# hive_module.net
KiCad netlist of a schematic drawn in EAGLE
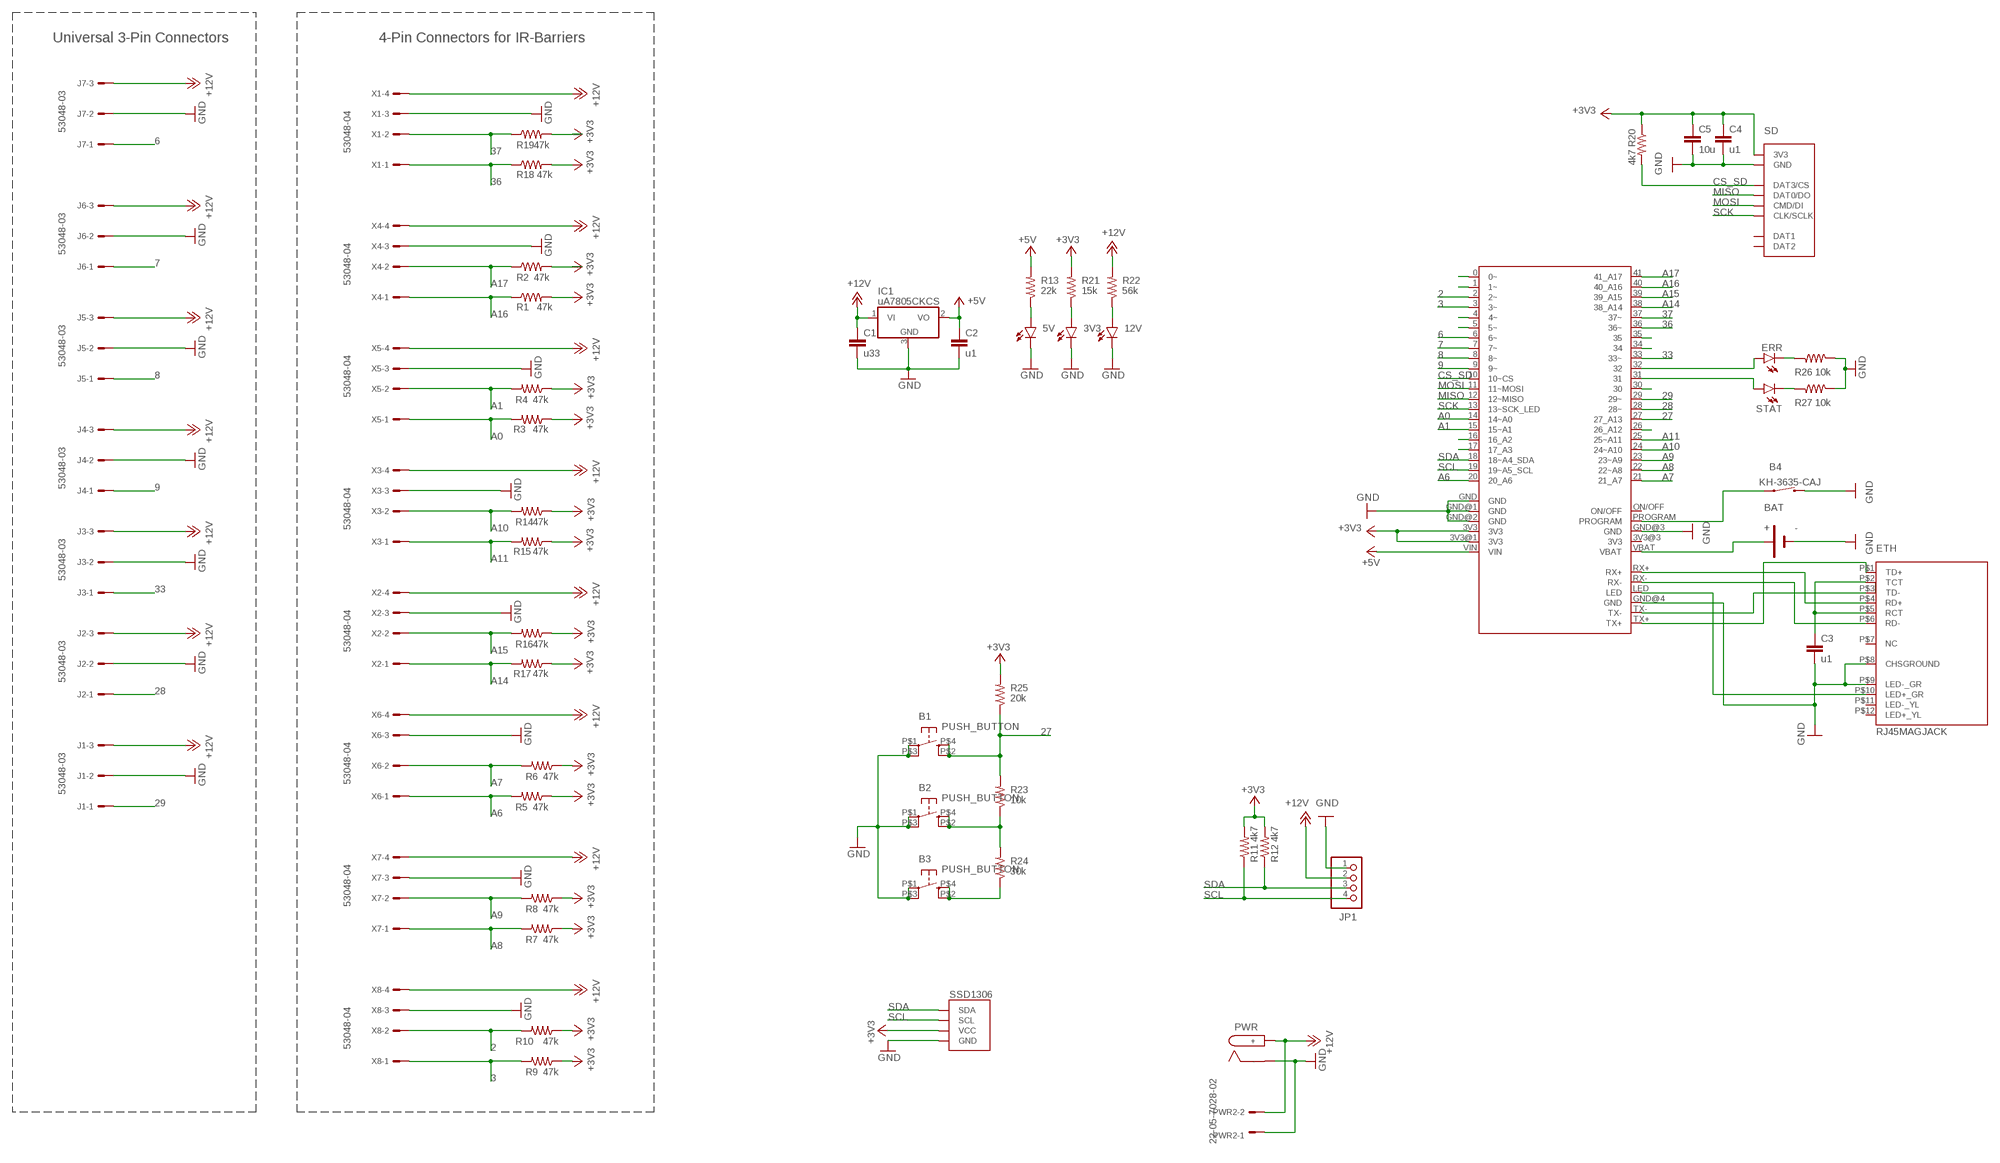
[diagram p0: schematic, sheet 1]

(export (version "E")
  (design (tool "Eeschema 10.0.6"))
  (components
    (comp (ref "3V3")
      (value "LEDCHIP-LED0805")
      (footprint "eagle-import:CHIP-LED0805")
      (libsource (lib "eagle-import") (part "LEDCHIP-LED0805"))
    )
    (comp (ref "5V")
      (value "LEDCHIP-LED0805")
      (footprint "eagle-import:CHIP-LED0805")
      (libsource (lib "eagle-import") (part "LEDCHIP-LED0805"))
    )
    (comp (ref "12V")
      (value "LEDCHIP-LED0805")
      (footprint "eagle-import:CHIP-LED0805")
      (libsource (lib "eagle-import") (part "LEDCHIP-LED0805"))
    )
    (comp (ref "B1")
      (value "PUSH_BUTTON")
      (footprint "eagle-import:PUSH_BUTTON")
      (libsource (lib "eagle-import") (part "PUSH_BUTTON"))
    )
    (comp (ref "B2")
      (value "PUSH_BUTTON")
      (footprint "eagle-import:PUSH_BUTTON")
      (libsource (lib "eagle-import") (part "PUSH_BUTTON"))
    )
    (comp (ref "B3")
      (value "PUSH_BUTTON")
      (footprint "eagle-import:PUSH_BUTTON")
      (libsource (lib "eagle-import") (part "PUSH_BUTTON"))
    )
    (comp (ref "B4")
      (value "KH-3635-CAJ")
      (footprint "eagle-import:KH-3635-CAJ")
      (libsource (lib "eagle-import") (part "KH-3635-CAJ"))
    )
    (comp (ref "BAT")
      (value "BS-08-B2AA002")
      (footprint "eagle-import:BS-08-B2AA002")
      (libsource (lib "eagle-import") (part "BS-08-B2AA002"))
    )
    (comp (ref "C1")
      (value "u33")
      (footprint "eagle-import:C0805")
      (libsource (lib "eagle-import") (part "C-EUC0805"))
    )
    (comp (ref "C2")
      (value "u1")
      (footprint "eagle-import:C0805")
      (libsource (lib "eagle-import") (part "C-EUC0805"))
    )
    (comp (ref "C3")
      (value "u1")
      (footprint "eagle-import:C0805")
      (libsource (lib "eagle-import") (part "C-EUC0805"))
    )
    (comp (ref "C4")
      (value "u1")
      (footprint "eagle-import:C0805")
      (libsource (lib "eagle-import") (part "C-EUC0805"))
    )
    (comp (ref "C5")
      (value "10u")
      (footprint "eagle-import:C0805")
      (libsource (lib "eagle-import") (part "C-EUC0805"))
    )
    (comp (ref "ERR")
      (value "LEDCHIP-LED0805")
      (footprint "eagle-import:CHIP-LED0805")
      (libsource (lib "eagle-import") (part "LEDCHIP-LED0805"))
    )
    (comp (ref "ETH")
      (value "RJ45MAGJACK")
      (footprint "eagle-import:LPJ4012AHNL")
      (libsource (lib "eagle-import") (part "RJ45MAGJACK"))
    )
    (comp (ref "IC1")
      (value "uA7805CKCS")
      (footprint "eagle-import:TO252")
      (libsource (lib "eagle-import") (part "7805_TO252"))
    )
    (comp (ref "J1")
      (value "53048-03")
      (footprint "eagle-import:53048-03")
      (fields (field (name "MF") "WALDOM/MOLEX") (field (name "MPN") "53048-0310"))
      (libsource (lib "eagle-import") (part "53?-03048"))
    )
    (comp (ref "J2")
      (value "53048-03")
      (footprint "eagle-import:53048-03")
      (fields (field (name "MF") "WALDOM/MOLEX") (field (name "MPN") "53048-0310"))
      (libsource (lib "eagle-import") (part "53?-03048"))
    )
    (comp (ref "J3")
      (value "53048-03")
      (footprint "eagle-import:53048-03")
      (fields (field (name "MF") "WALDOM/MOLEX") (field (name "MPN") "53048-0310"))
      (libsource (lib "eagle-import") (part "53?-03048"))
    )
    (comp (ref "J4")
      (value "53048-03")
      (footprint "eagle-import:53048-03")
      (fields (field (name "MF") "WALDOM/MOLEX") (field (name "MPN") "53048-0310"))
      (libsource (lib "eagle-import") (part "53?-03048"))
    )
    (comp (ref "J5")
      (value "53048-03")
      (footprint "eagle-import:53048-03")
      (fields (field (name "MF") "WALDOM/MOLEX") (field (name "MPN") "53048-0310"))
      (libsource (lib "eagle-import") (part "53?-03048"))
    )
    (comp (ref "J6")
      (value "53048-03")
      (footprint "eagle-import:53048-03")
      (fields (field (name "MF") "WALDOM/MOLEX") (field (name "MPN") "53048-0310"))
      (libsource (lib "eagle-import") (part "53?-03048"))
    )
    (comp (ref "J7")
      (value "53048-03")
      (footprint "eagle-import:53048-03")
      (fields (field (name "MF") "WALDOM/MOLEX") (field (name "MPN") "53048-0310"))
      (libsource (lib "eagle-import") (part "53?-03048"))
    )
    (comp (ref "JP1")
      (value "PINHD-1X4")
      (footprint "eagle-import:1X04")
      (libsource (lib "eagle-import") (part "PINHD-1X4"))
    )
    (comp (ref "PWR")
      (value "DC-042C-Z-2.5-A")
      (footprint "eagle-import:DC-042C-Z-2.5-A")
      (libsource (lib "eagle-import") (part "DC-042C-Z-2.5-A"))
    )
    (comp (ref "PWR2")
      (value "22-05-7028-02")
      (footprint "eagle-import:7395-02")
      (fields (field (name "MF") "MOLEX"))
      (libsource (lib "eagle-import") (part "22-?-0205-7028"))
    )
    (comp (ref "R1")
      (value "47k")
      (footprint "eagle-import:R0805")
      (libsource (lib "eagle-import") (part "R-US_R0805"))
    )
    (comp (ref "R2")
      (value "47k")
      (footprint "eagle-import:R0805")
      (libsource (lib "eagle-import") (part "R-US_R0805"))
    )
    (comp (ref "R3")
      (value "47k")
      (footprint "eagle-import:R0805")
      (libsource (lib "eagle-import") (part "R-US_R0805"))
    )
    (comp (ref "R4")
      (value "47k")
      (footprint "eagle-import:R0805")
      (libsource (lib "eagle-import") (part "R-US_R0805"))
    )
    (comp (ref "R5")
      (value "47k")
      (footprint "eagle-import:R0805")
      (libsource (lib "eagle-import") (part "R-US_R0805"))
    )
    (comp (ref "R6")
      (value "47k")
      (footprint "eagle-import:R0805")
      (libsource (lib "eagle-import") (part "R-US_R0805"))
    )
    (comp (ref "R7")
      (value "47k")
      (footprint "eagle-import:R0805")
      (libsource (lib "eagle-import") (part "R-US_R0805"))
    )
    (comp (ref "R8")
      (value "47k")
      (footprint "eagle-import:R0805")
      (libsource (lib "eagle-import") (part "R-US_R0805"))
    )
    (comp (ref "R9")
      (value "47k")
      (footprint "eagle-import:R0805")
      (libsource (lib "eagle-import") (part "R-US_R0805"))
    )
    (comp (ref "R10")
      (value "47k")
      (footprint "eagle-import:R0805")
      (libsource (lib "eagle-import") (part "R-US_R0805"))
    )
    (comp (ref "R11")
      (value "4k7")
      (footprint "eagle-import:R0805")
      (libsource (lib "eagle-import") (part "R-US_R0805"))
    )
    (comp (ref "R12")
      (value "4k7")
      (footprint "eagle-import:R0805")
      (libsource (lib "eagle-import") (part "R-US_R0805"))
    )
    (comp (ref "R13")
      (value "22k")
      (footprint "eagle-import:R0805")
      (libsource (lib "eagle-import") (part "R-US_R0805"))
    )
    (comp (ref "R14")
      (value "47k")
      (footprint "eagle-import:R0805")
      (libsource (lib "eagle-import") (part "R-US_R0805"))
    )
    (comp (ref "R15")
      (value "47k")
      (footprint "eagle-import:R0805")
      (libsource (lib "eagle-import") (part "R-US_R0805"))
    )
    (comp (ref "R16")
      (value "47k")
      (footprint "eagle-import:R0805")
      (libsource (lib "eagle-import") (part "R-US_R0805"))
    )
    (comp (ref "R17")
      (value "47k")
      (footprint "eagle-import:R0805")
      (libsource (lib "eagle-import") (part "R-US_R0805"))
    )
    (comp (ref "R18")
      (value "47k")
      (footprint "eagle-import:R0805")
      (libsource (lib "eagle-import") (part "R-US_R0805"))
    )
    (comp (ref "R19")
      (value "47k")
      (footprint "eagle-import:R0805")
      (libsource (lib "eagle-import") (part "R-US_R0805"))
    )
    (comp (ref "R20")
      (value "4k7")
      (footprint "eagle-import:R0805")
      (libsource (lib "eagle-import") (part "R-US_R0805"))
    )
    (comp (ref "R21")
      (value "15k")
      (footprint "eagle-import:R0805")
      (libsource (lib "eagle-import") (part "R-US_R0805"))
    )
    (comp (ref "R22")
      (value "56k")
      (footprint "eagle-import:R0805")
      (libsource (lib "eagle-import") (part "R-US_R0805"))
    )
    (comp (ref "R23")
      (value "10k")
      (footprint "eagle-import:R0805")
      (libsource (lib "eagle-import") (part "R-US_R0805"))
    )
    (comp (ref "R24")
      (value "30k")
      (footprint "eagle-import:R0805")
      (libsource (lib "eagle-import") (part "R-US_R0805"))
    )
    (comp (ref "R25")
      (value "20k")
      (footprint "eagle-import:R0805")
      (libsource (lib "eagle-import") (part "R-US_R0805"))
    )
    (comp (ref "R26")
      (value "10k")
      (footprint "eagle-import:R0805")
      (libsource (lib "eagle-import") (part "R-US_R0805"))
    )
    (comp (ref "R27")
      (value "10k")
      (footprint "eagle-import:R0805")
      (libsource (lib "eagle-import") (part "R-US_R0805"))
    )
    (comp (ref "SD")
      (value "TF-011")
      (footprint "eagle-import:TF-011")
      (libsource (lib "eagle-import") (part "TF-011"))
    )
    (comp (ref "SSD1306")
      (value "SSD1306")
      (footprint "eagle-import:SSD1306")
      (libsource (lib "eagle-import") (part "SSD1306"))
    )
    (comp (ref "STAT")
      (value "LEDCHIP-LED0805")
      (footprint "eagle-import:CHIP-LED0805")
      (libsource (lib "eagle-import") (part "LEDCHIP-LED0805"))
    )
    (comp (ref "U$1")
      (value "TEENSY41")
      (footprint "eagle-import:TEENSY41")
      (libsource (lib "eagle-import") (part "TEENSY41"))
    )
    (comp (ref "X1")
      (value "53048-04")
      (footprint "eagle-import:53048-04")
      (fields (field (name "MF") "MOLEX") (field (name "MPN") "53048-0410"))
      (libsource (lib "eagle-import") (part "53?-04048"))
    )
    (comp (ref "X2")
      (value "53048-04")
      (footprint "eagle-import:53048-04")
      (fields (field (name "MF") "MOLEX") (field (name "MPN") "53048-0410"))
      (libsource (lib "eagle-import") (part "53?-04048"))
    )
    (comp (ref "X3")
      (value "53048-04")
      (footprint "eagle-import:53048-04")
      (fields (field (name "MF") "MOLEX") (field (name "MPN") "53048-0410"))
      (libsource (lib "eagle-import") (part "53?-04048"))
    )
    (comp (ref "X4")
      (value "53048-04")
      (footprint "eagle-import:53048-04")
      (fields (field (name "MF") "MOLEX") (field (name "MPN") "53048-0410"))
      (libsource (lib "eagle-import") (part "53?-04048"))
    )
    (comp (ref "X5")
      (value "53048-04")
      (footprint "eagle-import:53048-04")
      (fields (field (name "MF") "MOLEX") (field (name "MPN") "53048-0410"))
      (libsource (lib "eagle-import") (part "53?-04048"))
    )
    (comp (ref "X6")
      (value "53048-04")
      (footprint "eagle-import:53048-04")
      (fields (field (name "MF") "MOLEX") (field (name "MPN") "53048-0410"))
      (libsource (lib "eagle-import") (part "53?-04048"))
    )
    (comp (ref "X7")
      (value "53048-04")
      (footprint "eagle-import:53048-04")
      (fields (field (name "MF") "MOLEX") (field (name "MPN") "53048-0410"))
      (libsource (lib "eagle-import") (part "53?-04048"))
    )
    (comp (ref "X8")
      (value "53048-04")
      (footprint "eagle-import:53048-04")
      (fields (field (name "MF") "MOLEX") (field (name "MPN") "53048-0410"))
      (libsource (lib "eagle-import") (part "53?-04048"))
    )
  )
  (nets
    (net (code "1") (name "+3V3") (class "Default")
      (node (ref "C4") (pin "1") (pinfunction "1_1") (pintype "passive"))
      (node (ref "C5") (pin "1") (pinfunction "1_1") (pintype "passive"))
      (node (ref "R1") (pin "2") (pinfunction "2_2") (pintype "passive"))
      (node (ref "R10") (pin "1") (pinfunction "1_1") (pintype "passive"))
      (node (ref "R11") (pin "2") (pinfunction "2_2") (pintype "passive"))
      (node (ref "R12") (pin "2") (pinfunction "2_2") (pintype "passive"))
      (node (ref "R14") (pin "1") (pinfunction "1_1") (pintype "passive"))
      (node (ref "R15") (pin "1") (pinfunction "1_1") (pintype "passive"))
      (node (ref "R16") (pin "1") (pinfunction "1_1") (pintype "passive"))
      (node (ref "R17") (pin "1") (pinfunction "1_1") (pintype "passive"))
      (node (ref "R18") (pin "2") (pinfunction "2_2") (pintype "passive"))
      (node (ref "R19") (pin "2") (pinfunction "2_2") (pintype "passive"))
      (node (ref "R2") (pin "2") (pinfunction "2_2") (pintype "passive"))
      (node (ref "R20") (pin "1") (pinfunction "1_1") (pintype "passive"))
      (node (ref "R21") (pin "2") (pinfunction "2_2") (pintype "passive"))
      (node (ref "R25") (pin "2") (pinfunction "2_2") (pintype "passive"))
      (node (ref "R3") (pin "1") (pinfunction "1_1") (pintype "passive"))
      (node (ref "R4") (pin "1") (pinfunction "1_1") (pintype "passive"))
      (node (ref "R5") (pin "1") (pinfunction "1_1") (pintype "passive"))
      (node (ref "R6") (pin "1") (pinfunction "1_1") (pintype "passive"))
      (node (ref "R7") (pin "1") (pinfunction "1_1") (pintype "passive"))
      (node (ref "R8") (pin "1") (pinfunction "1_1") (pintype "passive"))
      (node (ref "R9") (pin "1") (pinfunction "1_1") (pintype "passive"))
      (node (ref "SD") (pin "P$4") (pinfunction "3V3_P$4") (pintype "power_in"))
      (node (ref "SSD1306") (pin "P$2") (pinfunction "VCC_P$2") (pintype "power_in"))
      (node (ref "U$1") (pin "3V3") (pinfunction "3V3_3V3") (pintype "bidirectional"))
      (node (ref "U$1") (pin "3V3@1") (pinfunction "3V3_3V3@1") (pintype "bidirectional"))
    )
    (net (code "2") (name "+5V") (class "Default")
      (node (ref "C2") (pin "1") (pinfunction "1_1") (pintype "passive"))
      (node (ref "IC1") (pin "2") (pinfunction "VO_2") (pintype "passive"))
      (node (ref "R13") (pin "2") (pinfunction "2_2") (pintype "passive"))
      (node (ref "U$1") (pin "VIN") (pinfunction "VIN_VIN") (pintype "bidirectional"))
    )
    (net (code "3") (name "+12V") (class "Default")
      (node (ref "C1") (pin "1") (pinfunction "1_1") (pintype "passive"))
      (node (ref "IC1") (pin "1") (pinfunction "VI_1") (pintype "input"))
      (node (ref "J1") (pin "3") (pinfunction "S_3") (pintype "passive"))
      (node (ref "J2") (pin "3") (pinfunction "S_3") (pintype "passive"))
      (node (ref "J3") (pin "3") (pinfunction "S_3") (pintype "passive"))
      (node (ref "J4") (pin "3") (pinfunction "S_3") (pintype "passive"))
      (node (ref "J5") (pin "3") (pinfunction "S_3") (pintype "passive"))
      (node (ref "J6") (pin "3") (pinfunction "S_3") (pintype "passive"))
      (node (ref "J7") (pin "3") (pinfunction "S_3") (pintype "passive"))
      (node (ref "JP1") (pin "2") (pinfunction "2_2") (pintype "passive"))
      (node (ref "PWR") (pin "P$6") (pinfunction "+_P$6") (pintype "bidirectional"))
      (node (ref "PWR2") (pin "2") (pinfunction "S_2") (pintype "passive"))
      (node (ref "R22") (pin "2") (pinfunction "2_2") (pintype "passive"))
      (node (ref "X1") (pin "4") (pinfunction "S_4") (pintype "passive"))
      (node (ref "X2") (pin "4") (pinfunction "S_4") (pintype "passive"))
      (node (ref "X3") (pin "4") (pinfunction "S_4") (pintype "passive"))
      (node (ref "X4") (pin "4") (pinfunction "S_4") (pintype "passive"))
      (node (ref "X5") (pin "4") (pinfunction "S_4") (pintype "passive"))
      (node (ref "X6") (pin "4") (pinfunction "S_4") (pintype "passive"))
      (node (ref "X7") (pin "4") (pinfunction "S_4") (pintype "passive"))
      (node (ref "X8") (pin "4") (pinfunction "S_4") (pintype "passive"))
    )
    (net (code "4") (name "/2") (class "Default")
      (node (ref "R10") (pin "2") (pinfunction "2_2") (pintype "passive"))
      (node (ref "U$1") (pin "2") (pinfunction "2~{}_2") (pintype "bidirectional"))
      (node (ref "X8") (pin "2") (pinfunction "S_2") (pintype "passive"))
    )
    (net (code "5") (name "/3") (class "Default")
      (node (ref "R9") (pin "2") (pinfunction "2_2") (pintype "passive"))
      (node (ref "U$1") (pin "3") (pinfunction "3~{}_3") (pintype "bidirectional"))
      (node (ref "X8") (pin "1") (pinfunction "S_1") (pintype "passive"))
    )
    (net (code "6") (name "/6") (class "Default")
      (node (ref "J7") (pin "1") (pinfunction "S_1") (pintype "passive"))
      (node (ref "U$1") (pin "6") (pinfunction "6~{}_6") (pintype "bidirectional"))
    )
    (net (code "7") (name "/7") (class "Default")
      (node (ref "J6") (pin "1") (pinfunction "S_1") (pintype "passive"))
      (node (ref "U$1") (pin "7") (pinfunction "7~{}_7") (pintype "bidirectional"))
    )
    (net (code "8") (name "/8") (class "Default")
      (node (ref "J5") (pin "1") (pinfunction "S_1") (pintype "passive"))
      (node (ref "U$1") (pin "8") (pinfunction "8~{}_8") (pintype "bidirectional"))
    )
    (net (code "9") (name "/9") (class "Default")
      (node (ref "J4") (pin "1") (pinfunction "S_1") (pintype "passive"))
      (node (ref "U$1") (pin "9") (pinfunction "9~{}_9") (pintype "bidirectional"))
    )
    (net (code "10") (name "/27") (class "Default")
      (node (ref "B1") (pin "P$2") (pinfunction "S1_P$2") (pintype "passive"))
      (node (ref "B1") (pin "P$4") (pinfunction "S_P$4") (pintype "passive"))
      (node (ref "R23") (pin "2") (pinfunction "2_2") (pintype "passive"))
      (node (ref "R25") (pin "1") (pinfunction "1_1") (pintype "passive"))
      (node (ref "U$1") (pin "27") (pinfunction "27_A13_27") (pintype "bidirectional"))
    )
    (net (code "11") (name "/28") (class "Default")
      (node (ref "J2") (pin "1") (pinfunction "S_1") (pintype "passive"))
      (node (ref "U$1") (pin "28") (pinfunction "28~{}_28") (pintype "bidirectional"))
    )
    (net (code "12") (name "/29") (class "Default")
      (node (ref "J1") (pin "1") (pinfunction "S_1") (pintype "passive"))
      (node (ref "U$1") (pin "29") (pinfunction "29~{}_29") (pintype "bidirectional"))
    )
    (net (code "13") (name "/33") (class "Default")
      (node (ref "J3") (pin "1") (pinfunction "S_1") (pintype "passive"))
      (node (ref "U$1") (pin "33") (pinfunction "33~{}_33") (pintype "bidirectional"))
    )
    (net (code "14") (name "/36") (class "Default")
      (node (ref "R18") (pin "1") (pinfunction "1_1") (pintype "passive"))
      (node (ref "U$1") (pin "36") (pinfunction "36~{}_36") (pintype "bidirectional"))
      (node (ref "X1") (pin "1") (pinfunction "S_1") (pintype "passive"))
    )
    (net (code "15") (name "/37") (class "Default")
      (node (ref "R19") (pin "1") (pinfunction "1_1") (pintype "passive"))
      (node (ref "U$1") (pin "37") (pinfunction "37~{}_37") (pintype "bidirectional"))
      (node (ref "X1") (pin "2") (pinfunction "S_2") (pintype "passive"))
    )
    (net (code "16") (name "/A0") (class "Default")
      (node (ref "R3") (pin "2") (pinfunction "2_2") (pintype "passive"))
      (node (ref "U$1") (pin "14") (pinfunction "14~{A0}_14") (pintype "bidirectional"))
      (node (ref "X5") (pin "1") (pinfunction "S_1") (pintype "passive"))
    )
    (net (code "17") (name "/A1") (class "Default")
      (node (ref "R4") (pin "2") (pinfunction "2_2") (pintype "passive"))
      (node (ref "U$1") (pin "15") (pinfunction "15~{A1}_15") (pintype "bidirectional"))
      (node (ref "X5") (pin "2") (pinfunction "S_2") (pintype "passive"))
    )
    (net (code "18") (name "/A6") (class "Default")
      (node (ref "R5") (pin "2") (pinfunction "2_2") (pintype "passive"))
      (node (ref "U$1") (pin "20") (pinfunction "20_A6_20") (pintype "bidirectional"))
      (node (ref "X6") (pin "1") (pinfunction "S_1") (pintype "passive"))
    )
    (net (code "19") (name "/A7") (class "Default")
      (node (ref "R6") (pin "2") (pinfunction "2_2") (pintype "passive"))
      (node (ref "U$1") (pin "21") (pinfunction "21_A7_21") (pintype "bidirectional"))
      (node (ref "X6") (pin "2") (pinfunction "S_2") (pintype "passive"))
    )
    (net (code "20") (name "/A8") (class "Default")
      (node (ref "R7") (pin "2") (pinfunction "2_2") (pintype "passive"))
      (node (ref "U$1") (pin "22") (pinfunction "22~{A8}_22") (pintype "bidirectional"))
      (node (ref "X7") (pin "1") (pinfunction "S_1") (pintype "passive"))
    )
    (net (code "21") (name "/A9") (class "Default")
      (node (ref "R8") (pin "2") (pinfunction "2_2") (pintype "passive"))
      (node (ref "U$1") (pin "23") (pinfunction "23~{A9}_23") (pintype "bidirectional"))
      (node (ref "X7") (pin "2") (pinfunction "S_2") (pintype "passive"))
    )
    (net (code "22") (name "/A10") (class "Default")
      (node (ref "R14") (pin "2") (pinfunction "2_2") (pintype "passive"))
      (node (ref "U$1") (pin "24") (pinfunction "24~{A10}_24") (pintype "bidirectional"))
      (node (ref "X3") (pin "2") (pinfunction "S_2") (pintype "passive"))
    )
    (net (code "23") (name "/A11") (class "Default")
      (node (ref "R15") (pin "2") (pinfunction "2_2") (pintype "passive"))
      (node (ref "U$1") (pin "25") (pinfunction "25~{A11}_25") (pintype "bidirectional"))
      (node (ref "X3") (pin "1") (pinfunction "S_1") (pintype "passive"))
    )
    (net (code "24") (name "/A14") (class "Default")
      (node (ref "R17") (pin "2") (pinfunction "2_2") (pintype "passive"))
      (node (ref "U$1") (pin "38") (pinfunction "38_A14_38") (pintype "bidirectional"))
      (node (ref "X2") (pin "1") (pinfunction "S_1") (pintype "passive"))
    )
    (net (code "25") (name "/A15") (class "Default")
      (node (ref "R16") (pin "2") (pinfunction "2_2") (pintype "passive"))
      (node (ref "U$1") (pin "39") (pinfunction "39_A15_39") (pintype "bidirectional"))
      (node (ref "X2") (pin "2") (pinfunction "S_2") (pintype "passive"))
    )
    (net (code "26") (name "/A16") (class "Default")
      (node (ref "R1") (pin "1") (pinfunction "1_1") (pintype "passive"))
      (node (ref "U$1") (pin "40") (pinfunction "40_A16_40") (pintype "bidirectional"))
      (node (ref "X4") (pin "1") (pinfunction "S_1") (pintype "passive"))
    )
    (net (code "27") (name "/A17") (class "Default")
      (node (ref "R2") (pin "1") (pinfunction "1_1") (pintype "passive"))
      (node (ref "U$1") (pin "41") (pinfunction "41_A17_41") (pintype "bidirectional"))
      (node (ref "X4") (pin "2") (pinfunction "S_2") (pintype "passive"))
    )
    (net (code "28") (name "/CS_SD") (class "Default")
      (node (ref "R20") (pin "2") (pinfunction "2_2") (pintype "passive"))
      (node (ref "SD") (pin "P$2") (pinfunction "DAT3/CS_P$2") (pintype "bidirectional"))
      (node (ref "U$1") (pin "10") (pinfunction "10~{CS}_10") (pintype "bidirectional"))
    )
    (net (code "29") (name "/MISO") (class "Default")
      (node (ref "SD") (pin "P$7") (pinfunction "DAT0/DO_P$7") (pintype "bidirectional"))
      (node (ref "U$1") (pin "12") (pinfunction "12~{MISO}_12") (pintype "bidirectional"))
    )
    (net (code "30") (name "/MOSI") (class "Default")
      (node (ref "SD") (pin "P$3") (pinfunction "CMD/DI_P$3") (pintype "bidirectional"))
      (node (ref "U$1") (pin "11") (pinfunction "11~{MOSI}_11") (pintype "bidirectional"))
    )
    (net (code "31") (name "/SCK") (class "Default")
      (node (ref "SD") (pin "P$5") (pinfunction "CLK/SCLK_P$5") (pintype "bidirectional"))
      (node (ref "U$1") (pin "13") (pinfunction "13~{SCK_LED}_13") (pintype "bidirectional"))
    )
    (net (code "32") (name "/SCL") (class "Default")
      (node (ref "JP1") (pin "4") (pinfunction "4_4") (pintype "passive"))
      (node (ref "R11") (pin "1") (pinfunction "1_1") (pintype "passive"))
      (node (ref "SSD1306") (pin "P$3") (pinfunction "SCL_P$3") (pintype "bidirectional"))
      (node (ref "U$1") (pin "19") (pinfunction "19~{A5_SCL}_19") (pintype "bidirectional"))
    )
    (net (code "33") (name "/SDA") (class "Default")
      (node (ref "JP1") (pin "3") (pinfunction "3_3") (pintype "passive"))
      (node (ref "R12") (pin "1") (pinfunction "1_1") (pintype "passive"))
      (node (ref "SSD1306") (pin "P$4") (pinfunction "SDA_P$4") (pintype "bidirectional"))
      (node (ref "U$1") (pin "18") (pinfunction "18~{A4_SDA}_18") (pintype "bidirectional"))
    )
    (net (code "34") (name "GND") (class "Default")
      (node (ref "12V") (pin "C") (pinfunction "C_C") (pintype "passive"))
      (node (ref "3V3") (pin "C") (pinfunction "C_C") (pintype "passive"))
      (node (ref "5V") (pin "C") (pinfunction "C_C") (pintype "passive"))
      (node (ref "B1") (pin "P$1") (pinfunction "P_P$1") (pintype "passive"))
      (node (ref "B1") (pin "P$3") (pinfunction "P1_P$3") (pintype "passive"))
      (node (ref "B2") (pin "P$1") (pinfunction "P_P$1") (pintype "passive"))
      (node (ref "B2") (pin "P$3") (pinfunction "P1_P$3") (pintype "passive"))
      (node (ref "B3") (pin "P$1") (pinfunction "P_P$1") (pintype "passive"))
      (node (ref "B3") (pin "P$3") (pinfunction "P1_P$3") (pintype "passive"))
      (node (ref "B4") (pin "P$2") (pinfunction "2_P$2") (pintype "passive"))
      (node (ref "BAT") (pin "-") (pinfunction "-_-") (pintype "bidirectional"))
      (node (ref "C1") (pin "2") (pinfunction "2_2") (pintype "passive"))
      (node (ref "C2") (pin "2") (pinfunction "2_2") (pintype "passive"))
      (node (ref "C3") (pin "2") (pinfunction "2_2") (pintype "passive"))
      (node (ref "C4") (pin "2") (pinfunction "2_2") (pintype "passive"))
      (node (ref "C5") (pin "2") (pinfunction "2_2") (pintype "passive"))
      (node (ref "ETH") (pin "P$8") (pinfunction "CHSGROUND_P$8") (pintype "bidirectional"))
      (node (ref "ETH") (pin "P$9") (pinfunction "LED-_GR_P$9") (pintype "bidirectional"))
      (node (ref "IC1") (pin "3") (pinfunction "GND_3") (pintype "passive"))
      (node (ref "J1") (pin "2") (pinfunction "S_2") (pintype "passive"))
      (node (ref "J2") (pin "2") (pinfunction "S_2") (pintype "passive"))
      (node (ref "J3") (pin "2") (pinfunction "S_2") (pintype "passive"))
      (node (ref "J4") (pin "2") (pinfunction "S_2") (pintype "passive"))
      (node (ref "J5") (pin "2") (pinfunction "S_2") (pintype "passive"))
      (node (ref "J6") (pin "2") (pinfunction "S_2") (pintype "passive"))
      (node (ref "J7") (pin "2") (pinfunction "S_2") (pintype "passive"))
      (node (ref "JP1") (pin "1") (pinfunction "1_1") (pintype "passive"))
      (node (ref "PWR") (pin "P$1") (pinfunction "-_P$1") (pintype "bidirectional"))
      (node (ref "PWR") (pin "P$2") (pinfunction "-_P$2") (pintype "bidirectional"))
      (node (ref "PWR") (pin "P$3") (pinfunction "-_P$3") (pintype "bidirectional"))
      (node (ref "PWR") (pin "P$4") (pinfunction "-_P$4") (pintype "bidirectional"))
      (node (ref "PWR") (pin "P$5") (pinfunction "-_P$5") (pintype "bidirectional"))
      (node (ref "PWR2") (pin "1") (pinfunction "S_1") (pintype "passive"))
      (node (ref "R26") (pin "2") (pinfunction "2_2") (pintype "passive"))
      (node (ref "R27") (pin "2") (pinfunction "2_2") (pintype "passive"))
      (node (ref "SD") (pin "P$10") (pinfunction "GND_P$10") (pintype "power_in"))
      (node (ref "SD") (pin "P$11") (pinfunction "GND_P$11") (pintype "power_in"))
      (node (ref "SD") (pin "P$12") (pinfunction "GND_P$12") (pintype "power_in"))
      (node (ref "SD") (pin "P$6") (pinfunction "GND_P$6") (pintype "power_in"))
      (node (ref "SD") (pin "P$9") (pinfunction "GND_P$9") (pintype "power_in"))
      (node (ref "SSD1306") (pin "P$1") (pinfunction "GND_P$1") (pintype "power_in"))
      (node (ref "U$1") (pin "GND") (pinfunction "GND_GND") (pintype "bidirectional"))
      (node (ref "U$1") (pin "GND@1") (pinfunction "GND_GND@1") (pintype "bidirectional"))
      (node (ref "U$1") (pin "GND@2") (pinfunction "GND_GND@2") (pintype "bidirectional"))
      (node (ref "U$1") (pin "GND@3") (pinfunction "GND_GND@3") (pintype "bidirectional"))
      (node (ref "U$1") (pin "GND@4") (pinfunction "GND_GND@4") (pintype "bidirectional"))
      (node (ref "X1") (pin "3") (pinfunction "S_3") (pintype "passive"))
      (node (ref "X2") (pin "3") (pinfunction "S_3") (pintype "passive"))
      (node (ref "X3") (pin "3") (pinfunction "S_3") (pintype "passive"))
      (node (ref "X4") (pin "3") (pinfunction "S_3") (pintype "passive"))
      (node (ref "X5") (pin "3") (pinfunction "S_3") (pintype "passive"))
      (node (ref "X6") (pin "3") (pinfunction "S_3") (pintype "passive"))
      (node (ref "X7") (pin "3") (pinfunction "S_3") (pintype "passive"))
      (node (ref "X8") (pin "3") (pinfunction "S_3") (pintype "passive"))
    )
    (net (code "35") (name "Net-(3V3-PadA)") (class "Default")
      (node (ref "3V3") (pin "A") (pinfunction "A_A") (pintype "passive"))
      (node (ref "R21") (pin "1") (pinfunction "1_1") (pintype "passive"))
    )
    (net (code "36") (name "Net-(5V-PadA)") (class "Default")
      (node (ref "5V") (pin "A") (pinfunction "A_A") (pintype "passive"))
      (node (ref "R13") (pin "1") (pinfunction "1_1") (pintype "passive"))
    )
    (net (code "37") (name "Net-(12V-PadA)") (class "Default")
      (node (ref "12V") (pin "A") (pinfunction "A_A") (pintype "passive"))
      (node (ref "R22") (pin "1") (pinfunction "1_1") (pintype "passive"))
    )
    (net (code "38") (name "Net-(B2-S)") (class "Default")
      (node (ref "B2") (pin "P$2") (pinfunction "S1_P$2") (pintype "passive"))
      (node (ref "B2") (pin "P$4") (pinfunction "S_P$4") (pintype "passive"))
      (node (ref "R23") (pin "1") (pinfunction "1_1") (pintype "passive"))
      (node (ref "R24") (pin "2") (pinfunction "2_2") (pintype "passive"))
    )
    (net (code "39") (name "Net-(B3-S)") (class "Default")
      (node (ref "B3") (pin "P$2") (pinfunction "S1_P$2") (pintype "passive"))
      (node (ref "B3") (pin "P$4") (pinfunction "S_P$4") (pintype "passive"))
      (node (ref "R24") (pin "1") (pinfunction "1_1") (pintype "passive"))
    )
    (net (code "40") (name "Net-(B4-1)") (class "Default")
      (node (ref "B4") (pin "P$1") (pinfunction "1_P$1") (pintype "passive"))
      (node (ref "U$1") (pin "PROGRAM") (pinfunction "PROGRAM_PROGRAM") (pintype "bidirectional"))
    )
    (net (code "41") (name "Net-(BAT-Pad+)") (class "Default")
      (node (ref "BAT") (pin "+") (pinfunction "+_+") (pintype "bidirectional"))
      (node (ref "U$1") (pin "VBAT") (pinfunction "VBAT_VBAT") (pintype "bidirectional"))
    )
    (net (code "42") (name "Net-(ERR-PadA)") (class "Default")
      (node (ref "ERR") (pin "A") (pinfunction "A_A") (pintype "passive"))
      (node (ref "U$1") (pin "32") (pinfunction "32_32") (pintype "bidirectional"))
    )
    (net (code "43") (name "Net-(ERR-PadC)") (class "Default")
      (node (ref "ERR") (pin "C") (pinfunction "C_C") (pintype "passive"))
      (node (ref "R26") (pin "1") (pinfunction "1_1") (pintype "passive"))
    )
    (net (code "44") (name "Net-(ETH-LED+_GR)") (class "Default")
      (node (ref "ETH") (pin "P$10") (pinfunction "LED+_GR_P$10") (pintype "bidirectional"))
      (node (ref "U$1") (pin "LED") (pinfunction "LED_LED") (pintype "bidirectional"))
    )
    (net (code "45") (name "Net-(ETH-RCT)") (class "Default")
      (node (ref "C3") (pin "1") (pinfunction "1_1") (pintype "passive"))
      (node (ref "ETH") (pin "P$2") (pinfunction "TCT_P$2") (pintype "bidirectional"))
      (node (ref "ETH") (pin "P$5") (pinfunction "RCT_P$5") (pintype "bidirectional"))
    )
    (net (code "46") (name "Net-(ETH-RD+)") (class "Default")
      (node (ref "ETH") (pin "P$4") (pinfunction "RD+_P$4") (pintype "bidirectional"))
      (node (ref "U$1") (pin "RX+") (pinfunction "RX+_RX+") (pintype "bidirectional"))
    )
    (net (code "47") (name "Net-(ETH-RD-)") (class "Default")
      (node (ref "ETH") (pin "P$6") (pinfunction "RD-_P$6") (pintype "bidirectional"))
      (node (ref "U$1") (pin "RX-") (pinfunction "RX-_RX-") (pintype "bidirectional"))
    )
    (net (code "48") (name "Net-(ETH-TD+)") (class "Default")
      (node (ref "ETH") (pin "P$1") (pinfunction "TD+_P$1") (pintype "bidirectional"))
      (node (ref "U$1") (pin "TX+") (pinfunction "TX+_TX+") (pintype "bidirectional"))
    )
    (net (code "49") (name "Net-(ETH-TD-)") (class "Default")
      (node (ref "ETH") (pin "P$3") (pinfunction "TD-_P$3") (pintype "bidirectional"))
      (node (ref "U$1") (pin "TX-") (pinfunction "TX-_TX-") (pintype "bidirectional"))
    )
    (net (code "50") (name "Net-(R27-Pad1)") (class "Default")
      (node (ref "R27") (pin "1") (pinfunction "1_1") (pintype "passive"))
      (node (ref "STAT") (pin "C") (pinfunction "C_C") (pintype "passive"))
    )
    (net (code "51") (name "Net-(STAT-PadA)") (class "Default")
      (node (ref "STAT") (pin "A") (pinfunction "A_A") (pintype "passive"))
      (node (ref "U$1") (pin "31") (pinfunction "31_31") (pintype "bidirectional"))
    )
    (net (code "52") (name "unconnected-(ETH-LED+_YL-PadP$12)") (class "Default")
      (node (ref "ETH") (pin "P$12") (pinfunction "LED+_YL_P$12") (pintype "bidirectional"))
    )
    (net (code "53") (name "unconnected-(ETH-LED-_YL-PadP$11)") (class "Default")
      (node (ref "ETH") (pin "P$11") (pinfunction "LED-_YL_P$11") (pintype "bidirectional"))
    )
    (net (code "54") (name "unconnected-(ETH-NC-PadP$7)") (class "Default")
      (node (ref "ETH") (pin "P$7") (pinfunction "NC_P$7") (pintype "bidirectional"))
    )
    (net (code "55") (name "unconnected-(SD-DAT1-PadP$8)") (class "Default")
      (node (ref "SD") (pin "P$8") (pinfunction "DAT1_P$8") (pintype "bidirectional"))
    )
    (net (code "56") (name "unconnected-(SD-DAT2-PadP$1)") (class "Default")
      (node (ref "SD") (pin "P$1") (pinfunction "DAT2_P$1") (pintype "bidirectional"))
    )
    (net (code "57") (name "unconnected-(U$1-0~{}-Pad0)") (class "Default")
      (node (ref "U$1") (pin "0") (pinfunction "0~{}_0") (pintype "bidirectional"))
    )
    (net (code "58") (name "unconnected-(U$1-1~{}-Pad1)") (class "Default")
      (node (ref "U$1") (pin "1") (pinfunction "1~{}_1") (pintype "bidirectional"))
    )
    (net (code "59") (name "unconnected-(U$1-3V3-Pad3V3@3)") (class "Default")
      (node (ref "U$1") (pin "3V3@3") (pinfunction "3V3_3V3@3") (pintype "bidirectional"))
    )
    (net (code "60") (name "unconnected-(U$1-4~{}-Pad4)") (class "Default")
      (node (ref "U$1") (pin "4") (pinfunction "4~{}_4") (pintype "bidirectional"))
    )
    (net (code "61") (name "unconnected-(U$1-5~{}-Pad5)") (class "Default")
      (node (ref "U$1") (pin "5") (pinfunction "5~{}_5") (pintype "bidirectional"))
    )
    (net (code "62") (name "unconnected-(U$1-16_A2-Pad16)") (class "Default")
      (node (ref "U$1") (pin "16") (pinfunction "16_A2_16") (pintype "bidirectional"))
    )
    (net (code "63") (name "unconnected-(U$1-17_A3-Pad17)") (class "Default")
      (node (ref "U$1") (pin "17") (pinfunction "17_A3_17") (pintype "bidirectional"))
    )
    (net (code "64") (name "unconnected-(U$1-26_A12-Pad26)") (class "Default")
      (node (ref "U$1") (pin "26") (pinfunction "26_A12_26") (pintype "bidirectional"))
    )
    (net (code "65") (name "unconnected-(U$1-Pad30)") (class "Default")
      (node (ref "U$1") (pin "30") (pinfunction "30_30") (pintype "bidirectional"))
    )
    (net (code "66") (name "unconnected-(U$1-Pad34)") (class "Default")
      (node (ref "U$1") (pin "34") (pinfunction "34_34") (pintype "bidirectional"))
    )
    (net (code "67") (name "unconnected-(U$1-Pad35)") (class "Default")
      (node (ref "U$1") (pin "35") (pinfunction "35_35") (pintype "bidirectional"))
    )
    (net (code "68") (name "unconnected-(U$1-PadON{slash}OFF)") (class "Default")
      (node (ref "U$1") (pin "ON/OFF") (pinfunction "ON/OFF_ON/OFF") (pintype "bidirectional"))
    )
  )
)
